# familab_pov.net
KiCad netlist of a schematic drawn in EAGLE
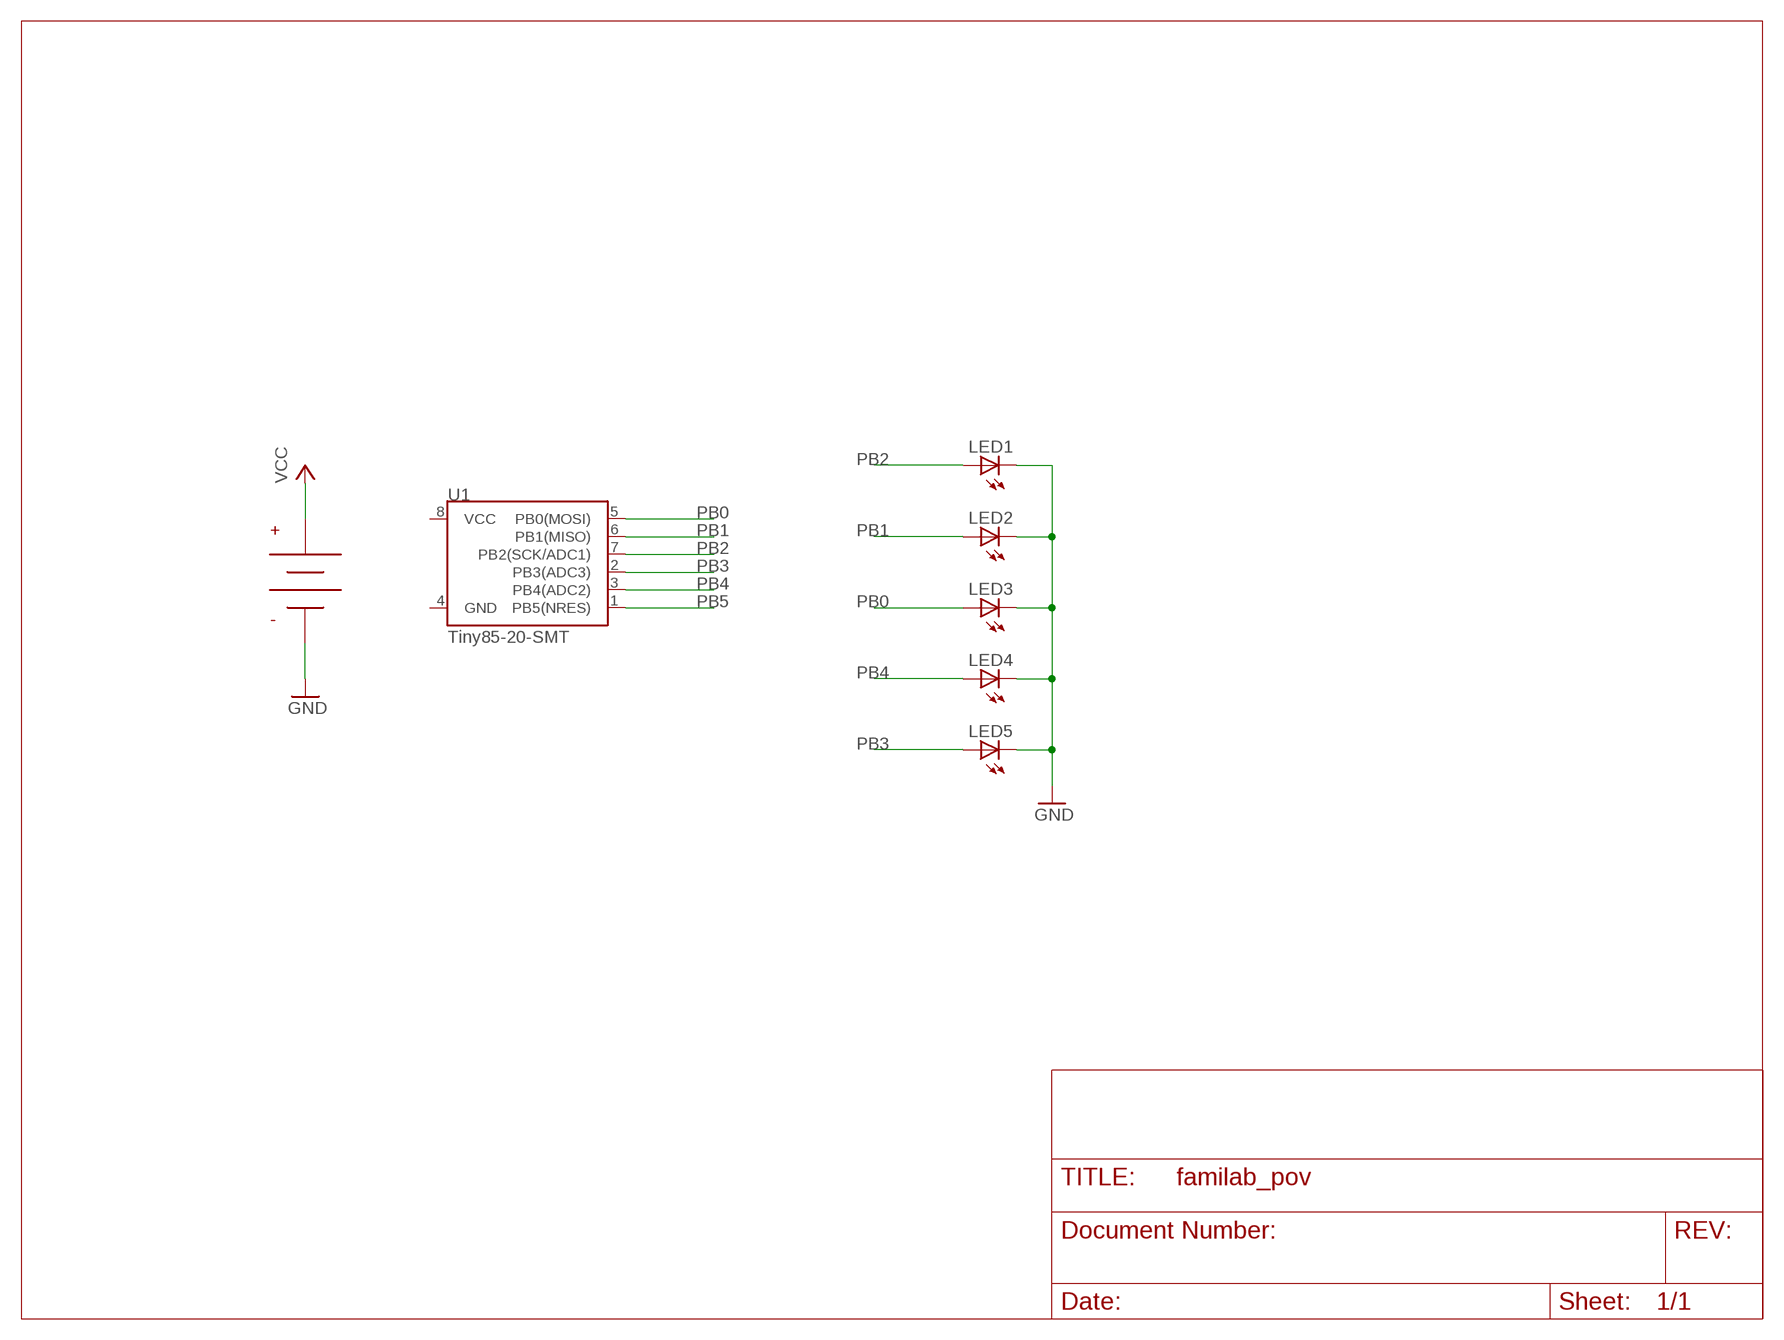
[diagram p0: schematic, sheet 1]

(export (version "E")
  (design (tool "Eeschema 10.0.6"))
  (components
    (comp (ref "LED1")
      (value "LED")
      (footprint "eagle-import:LED5MM_SMD_SIDE")
      (libsource (lib "eagle-import") (part "LED"))
    )
    (comp (ref "LED2")
      (value "LED")
      (footprint "eagle-import:LED5MM_SMD_SIDE")
      (libsource (lib "eagle-import") (part "LED"))
    )
    (comp (ref "LED3")
      (value "LED")
      (footprint "eagle-import:LED5MM_SMD_SIDE")
      (libsource (lib "eagle-import") (part "LED"))
    )
    (comp (ref "LED4")
      (value "LED")
      (footprint "eagle-import:LED5MM_SMD_SIDE")
      (libsource (lib "eagle-import") (part "LED"))
    )
    (comp (ref "LED5")
      (value "LED")
      (footprint "eagle-import:LED5MM_SMD_SIDE")
      (libsource (lib "eagle-import") (part "LED"))
    )
    (comp (ref "U$1")
      (value "CR2032_HOLDER")
      (footprint "eagle-import:CR2032_BC2032-F1")
      (libsource (lib "eagle-import") (part "CR2032_HOLDER"))
    )
    (comp (ref "U1")
      (value "Tiny85-20-SMT")
      (footprint "eagle-import:SO08-EIAJ")
      (libsource (lib "eagle-import") (part "ATTINY45TINY85-20-SMT"))
    )
  )
  (nets
    (net (code "1") (name "/PB0") (class "Default")
      (node (ref "LED3") (pin "A") (pinfunction "A_A") (pintype "passive"))
      (node (ref "U1") (pin "5") (pinfunction "PB0(MOSI)_5") (pintype "bidirectional"))
    )
    (net (code "2") (name "/PB1") (class "Default")
      (node (ref "LED2") (pin "A") (pinfunction "A_A") (pintype "passive"))
      (node (ref "U1") (pin "6") (pinfunction "PB1(MISO)_6") (pintype "bidirectional"))
    )
    (net (code "3") (name "/PB2") (class "Default")
      (node (ref "LED1") (pin "A") (pinfunction "A_A") (pintype "passive"))
      (node (ref "U1") (pin "7") (pinfunction "PB2(SCK/ADC1)_7") (pintype "bidirectional"))
    )
    (net (code "4") (name "/PB3") (class "Default")
      (node (ref "LED5") (pin "A") (pinfunction "A_A") (pintype "passive"))
      (node (ref "U1") (pin "2") (pinfunction "PB3(ADC3)_2") (pintype "bidirectional"))
    )
    (net (code "5") (name "/PB4") (class "Default")
      (node (ref "LED4") (pin "A") (pinfunction "A_A") (pintype "passive"))
      (node (ref "U1") (pin "3") (pinfunction "PB4(ADC2)_3") (pintype "bidirectional"))
    )
    (net (code "6") (name "/PB5") (class "Default")
      (node (ref "U1") (pin "1") (pinfunction "PB5(NRES)_1") (pintype "bidirectional"))
    )
    (net (code "7") (name "GND") (class "Default")
      (node (ref "LED1") (pin "C") (pinfunction "C_C") (pintype "passive"))
      (node (ref "LED2") (pin "C") (pinfunction "C_C") (pintype "passive"))
      (node (ref "LED3") (pin "C") (pinfunction "C_C") (pintype "passive"))
      (node (ref "LED4") (pin "C") (pinfunction "C_C") (pintype "passive"))
      (node (ref "LED5") (pin "C") (pinfunction "C_C") (pintype "passive"))
      (node (ref "U$1") (pin "NEG") (pinfunction "NEG_NEG") (pintype "bidirectional"))
    )
    (net (code "8") (name "VCC") (class "Default")
      (node (ref "U$1") (pin "POS") (pinfunction "POS_POS") (pintype "bidirectional"))
    )
    (net (code "9") (name "unconnected-(U1-GND-Pad4)") (class "Default")
      (node (ref "U1") (pin "4") (pinfunction "GND_4") (pintype "bidirectional"))
    )
    (net (code "10") (name "unconnected-(U1-VCC-Pad8)") (class "Default")
      (node (ref "U1") (pin "8") (pinfunction "VCC_8") (pintype "bidirectional"))
    )
  )
)
